# MQ303A_EEPROM_v4_0_-_para_testes.net
KiCad netlist of a schematic drawn in EAGLE
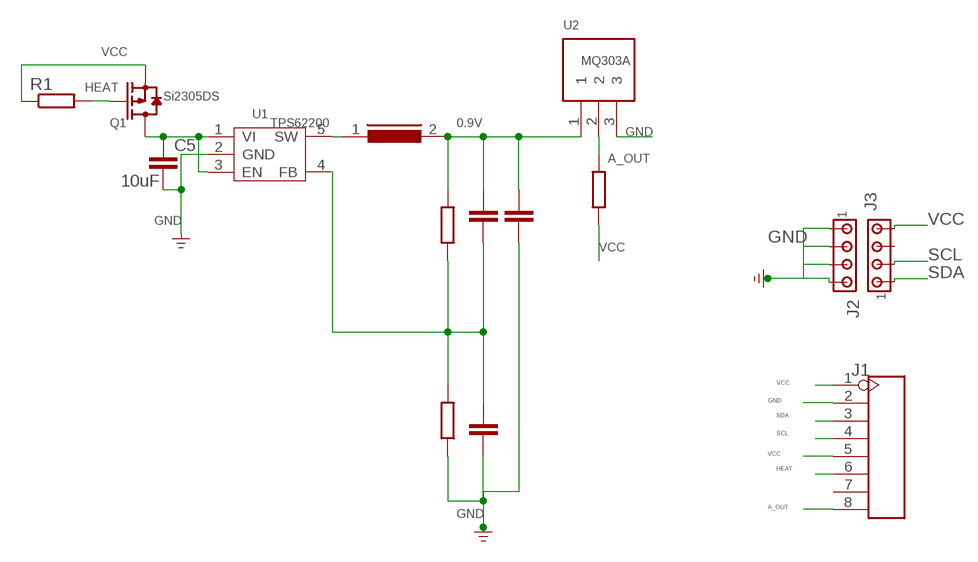
[diagram p0: schematic, sheet 1]

(export (version "E")
  (design (tool "Eeschema 10.0.6"))
  (components
    (comp (ref "C1")
      (value "10uF")
      (footprint "eagle-import:C050-025X075")
      (libsource (lib "eagle-import") (part "C-EU050-025X075"))
    )
    (comp (ref "C2")
      (value "10uF")
      (footprint "eagle-import:C050-025X075")
      (libsource (lib "eagle-import") (part "C-EU050-025X075"))
    )
    (comp (ref "C3")
      (value "10uF")
      (footprint "eagle-import:C050-025X075")
      (libsource (lib "eagle-import") (part "C-EU050-025X075"))
    )
    (comp (ref "C5")
      (value "10uF")
      (footprint "eagle-import:C050-025X075")
      (libsource (lib "eagle-import") (part "C-EU050-025X075"))
    )
    (comp (ref "J1")
      (value "HEADER-8P-2.54")
      (footprint "eagle-import:8P-2.54")
      (libsource (lib "eagle-import") (part "HEADER-8P-2.54"))
    )
    (comp (ref "J2")
      (value "MTA04-100")
      (footprint "eagle-import:10X04MTA")
      (libsource (lib "eagle-import") (part "MTA04-100"))
    )
    (comp (ref "J3")
      (value "MTA04-100")
      (footprint "eagle-import:10X04MTA")
      (libsource (lib "eagle-import") (part "MTA04-100"))
    )
    (comp (ref "L2")
      (value "MMICC7")
      (footprint "eagle-import:MMICC7")
      (libsource (lib "eagle-import") (part "MMICC7"))
    )
    (comp (ref "Q1")
      (value "Si2305DS")
      (footprint "eagle-import:SOT23")
      (libsource (lib "eagle-import") (part "MOSFET-P'SI2323CDS/SI2305DS{lt}BR{gt}'"))
    )
    (comp (ref "R1")
      (value "R-EU_0207/10")
      (footprint "eagle-import:0207_10")
      (libsource (lib "eagle-import") (part "R-EU_0207/10"))
    )
    (comp (ref "R2")
      (value "R-EU_0207/10")
      (footprint "eagle-import:0207_10")
      (libsource (lib "eagle-import") (part "R-EU_0207/10"))
    )
    (comp (ref "R3")
      (value "R-EU_0207/10")
      (footprint "eagle-import:0207_10")
      (libsource (lib "eagle-import") (part "R-EU_0207/10"))
    )
    (comp (ref "R5")
      (value "R-EU_0207/10")
      (footprint "eagle-import:0207_10")
      (libsource (lib "eagle-import") (part "R-EU_0207/10"))
    )
    (comp (ref "U1")
      (value "TPS62200")
      (footprint "eagle-import:SOT23-5")
      (libsource (lib "eagle-import") (part "TPS62200DBV"))
    )
    (comp (ref "U2")
      (value "MQ303A")
      (footprint "eagle-import:MQ303A")
      (libsource (lib "eagle-import") (part "MQ303A"))
    )
  )
  (nets
    (net (code "1") (name "/0.9V") (class "Default")
      (node (ref "C1") (pin "1") (pinfunction "1_1") (pintype "passive"))
      (node (ref "C3") (pin "1") (pinfunction "1_1") (pintype "passive"))
      (node (ref "L2") (pin "2") (pinfunction "2_2") (pintype "passive"))
      (node (ref "R5") (pin "2") (pinfunction "2_2") (pintype "passive"))
      (node (ref "U2") (pin "1") (pinfunction "1_1") (pintype "bidirectional"))
    )
    (net (code "2") (name "/A_OUT") (class "Default")
      (node (ref "J1") (pin "8") (pinfunction "8_8") (pintype "bidirectional"))
      (node (ref "R3") (pin "2") (pinfunction "2_2") (pintype "passive"))
      (node (ref "U2") (pin "2") (pinfunction "2_2") (pintype "bidirectional"))
    )
    (net (code "3") (name "/HEAT") (class "Default")
      (node (ref "J1") (pin "6") (pinfunction "6_6") (pintype "bidirectional"))
      (node (ref "Q1") (pin "1") (pinfunction "G_1") (pintype "passive"))
      (node (ref "R1") (pin "2") (pinfunction "2_2") (pintype "passive"))
    )
    (net (code "4") (name "/SCL") (class "Default")
      (node (ref "J1") (pin "4") (pinfunction "4_4") (pintype "bidirectional"))
      (node (ref "J3") (pin "2") (pinfunction "2_2") (pintype "passive"))
    )
    (net (code "5") (name "/SDA") (class "Default")
      (node (ref "J1") (pin "3") (pinfunction "3_3") (pintype "bidirectional"))
      (node (ref "J3") (pin "1") (pinfunction "1_1") (pintype "passive"))
    )
    (net (code "6") (name "/VCC") (class "Default")
      (node (ref "J1") (pin "1") (pinfunction "1_1") (pintype "bidirectional"))
      (node (ref "J1") (pin "5") (pinfunction "5_5") (pintype "bidirectional"))
      (node (ref "J3") (pin "4") (pinfunction "4_4") (pintype "passive"))
      (node (ref "Q1") (pin "2") (pinfunction "S_2") (pintype "passive"))
      (node (ref "R1") (pin "1") (pinfunction "1_1") (pintype "passive"))
      (node (ref "R3") (pin "1") (pinfunction "1_1") (pintype "passive"))
    )
    (net (code "7") (name "GND_POWER") (class "Default")
      (node (ref "C2") (pin "2") (pinfunction "2_2") (pintype "passive"))
      (node (ref "C3") (pin "2") (pinfunction "2_2") (pintype "passive"))
      (node (ref "C5") (pin "2") (pinfunction "2_2") (pintype "passive"))
      (node (ref "J1") (pin "2") (pinfunction "2_2") (pintype "bidirectional"))
      (node (ref "J2") (pin "1") (pinfunction "1_1") (pintype "passive"))
      (node (ref "J2") (pin "2") (pinfunction "2_2") (pintype "passive"))
      (node (ref "J2") (pin "3") (pinfunction "3_3") (pintype "passive"))
      (node (ref "J2") (pin "4") (pinfunction "4_4") (pintype "passive"))
      (node (ref "R2") (pin "1") (pinfunction "1_1") (pintype "passive"))
      (node (ref "U1") (pin "2") (pinfunction "GND_2") (pintype "power_in"))
      (node (ref "U2") (pin "3") (pinfunction "3_3") (pintype "bidirectional"))
    )
    (net (code "8") (name "Net-(Q1-D)") (class "Default")
      (node (ref "C5") (pin "1") (pinfunction "1_1") (pintype "passive"))
      (node (ref "Q1") (pin "3") (pinfunction "D_3") (pintype "passive"))
      (node (ref "U1") (pin "1") (pinfunction "VI_1") (pintype "input"))
      (node (ref "U1") (pin "3") (pinfunction "EN_3") (pintype "input"))
    )
    (net (code "9") (name "Net-(U1-FB)") (class "Default")
      (node (ref "C1") (pin "2") (pinfunction "2_2") (pintype "passive"))
      (node (ref "C2") (pin "1") (pinfunction "1_1") (pintype "passive"))
      (node (ref "R2") (pin "2") (pinfunction "2_2") (pintype "passive"))
      (node (ref "R5") (pin "1") (pinfunction "1_1") (pintype "passive"))
      (node (ref "U1") (pin "4") (pinfunction "FB_4") (pintype "input"))
    )
    (net (code "10") (name "Net-(U1-SW)") (class "Default")
      (node (ref "L2") (pin "1") (pinfunction "1_1") (pintype "passive"))
      (node (ref "U1") (pin "5") (pinfunction "SW_5") (pintype "bidirectional"))
    )
    (net (code "11") (name "unconnected-(J1-Pad7)") (class "Default")
      (node (ref "J1") (pin "7") (pinfunction "7_7") (pintype "bidirectional"))
    )
    (net (code "12") (name "unconnected-(J3-Pad3)") (class "Default")
      (node (ref "J3") (pin "3") (pinfunction "3_3") (pintype "passive"))
    )
  )
)
